# Digital_Online_Clock.net
KiCad netlist of a schematic drawn in EasyEDA Pro
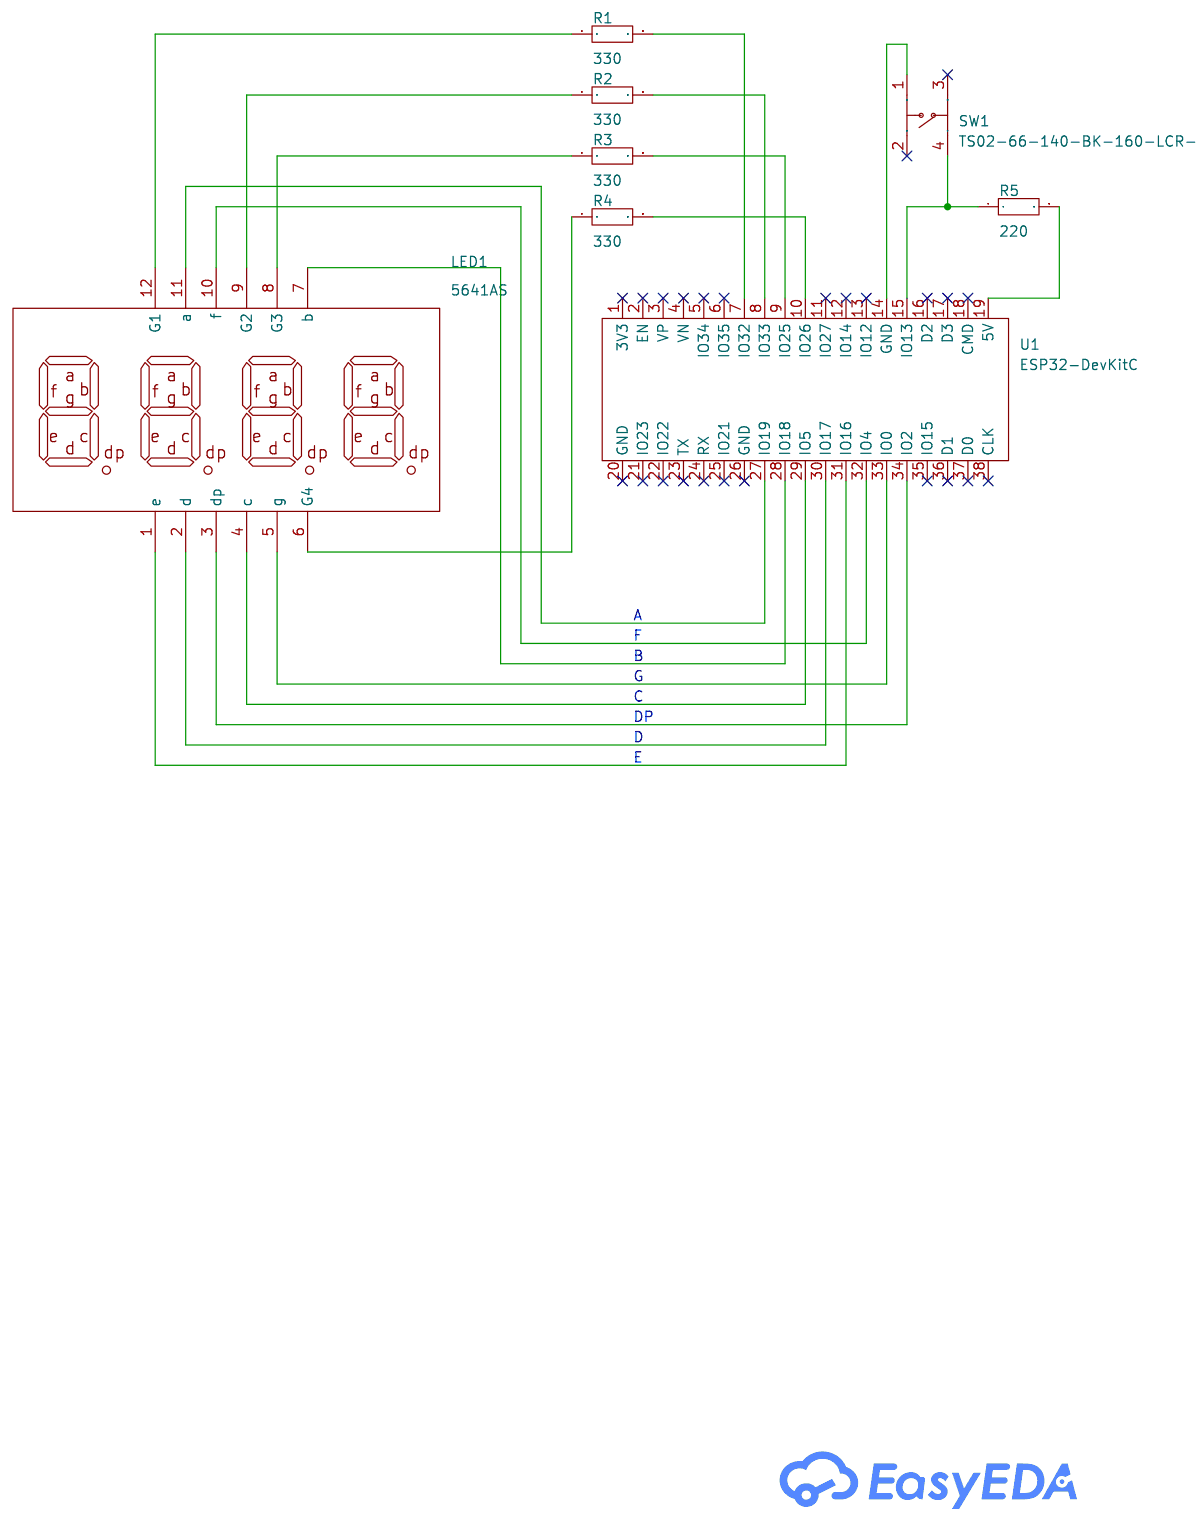
[diagram p0: schematic sheet]

(export (version "E")
  (design (tool "Eeschema 10.0.6"))
  (components
    (comp (ref "LED1")
      (value "5641AS")
      (footprint "easyedapro:LED-SEG-50x19x8mm")
      (description "Illumination Color:-")
      (fields (field (name "Manufacturer Part") "SR420312N/32") (field (name "Manufacturer") "ARKLED(方舟)"))
      (libsource (lib "easyedapro") (part "SR420312N/32"))
    )
    (comp (ref "R1") (value "330") (footprint "easyedapro:R0603") (libsource (lib "easyedapro") (part "Res")))
    (comp (ref "R2") (value "330") (footprint "easyedapro:R0603") (libsource (lib "easyedapro") (part "Res")))
    (comp (ref "R3") (value "330") (footprint "easyedapro:R0603") (libsource (lib "easyedapro") (part "Res")))
    (comp (ref "R4") (value "330") (footprint "easyedapro:R0603") (libsource (lib "easyedapro") (part "Res")))
    (comp (ref "R5") (value "220") (footprint "easyedapro:R0603") (libsource (lib "easyedapro") (part "Res")))
    (comp (ref "SW1")
      (value "TS02-66-140-BK-160-LCR-D")
      (footprint "easyedapro:SW-TH_4P-L6.0-W6.0-P4.50-LS6.5")
      (fields (field (name "Manufacturer") "CUI Devices"))
      (libsource (lib "easyedapro") (part "TS02-66-140-BK-160-LCR-D"))
    )
    (comp (ref "U1")
      (value "ESP32-DevKitC")
      (footprint "easyedapro:BULETM-SMD_ESP32-DEVKITC")
      (fields (field (name "Manufacturer") "ESPRESSIF(乐鑫)"))
      (libsource (lib "easyedapro") (part "ESP32-DEVKITC"))
    )
  )
  (nets
    (net (code "1") (name "Net-(LED1-G1)") (class "Default")
      (node (ref "LED1") (pin "12") (pinfunction "G1_12") (pintype "input"))
      (node (ref "R1") (pin "1") (pinfunction "1_1") (pintype "input"))
    )
    (net (code "2") (name "Net-(LED1-G2)") (class "Default")
      (node (ref "LED1") (pin "9") (pinfunction "G2_9") (pintype "input"))
      (node (ref "R2") (pin "1") (pinfunction "1_1") (pintype "input"))
    )
    (net (code "3") (name "Net-(LED1-G3)") (class "Default")
      (node (ref "LED1") (pin "8") (pinfunction "G3_8") (pintype "input"))
      (node (ref "R3") (pin "1") (pinfunction "1_1") (pintype "input"))
    )
    (net (code "4") (name "Net-(LED1-G4)") (class "Default")
      (node (ref "LED1") (pin "6") (pinfunction "G4_6") (pintype "input"))
      (node (ref "R4") (pin "1") (pinfunction "1_1") (pintype "input"))
    )
    (net (code "5") (name "Net-(LED1-a)") (class "Default")
      (node (ref "LED1") (pin "11") (pinfunction "a_11") (pintype "input"))
      (node (ref "U1") (pin "27") (pinfunction "IO19_27") (pintype "unspecified"))
    )
    (net (code "6") (name "Net-(LED1-b)") (class "Default")
      (node (ref "LED1") (pin "7") (pinfunction "b_7") (pintype "input"))
      (node (ref "U1") (pin "28") (pinfunction "IO18_28") (pintype "unspecified"))
    )
    (net (code "7") (name "Net-(LED1-c)") (class "Default")
      (node (ref "LED1") (pin "4") (pinfunction "c_4") (pintype "input"))
      (node (ref "U1") (pin "29") (pinfunction "IO5_29") (pintype "unspecified"))
    )
    (net (code "8") (name "Net-(LED1-d)") (class "Default")
      (node (ref "LED1") (pin "2") (pinfunction "d_2") (pintype "input"))
      (node (ref "U1") (pin "30") (pinfunction "IO17_30") (pintype "unspecified"))
    )
    (net (code "9") (name "Net-(LED1-dp)") (class "Default")
      (node (ref "LED1") (pin "3") (pinfunction "dp_3") (pintype "input"))
      (node (ref "U1") (pin "34") (pinfunction "IO2_34") (pintype "unspecified"))
    )
    (net (code "10") (name "Net-(LED1-e)") (class "Default")
      (node (ref "LED1") (pin "1") (pinfunction "e_1") (pintype "input"))
      (node (ref "U1") (pin "31") (pinfunction "IO16_31") (pintype "unspecified"))
    )
    (net (code "11") (name "Net-(LED1-f)") (class "Default")
      (node (ref "LED1") (pin "10") (pinfunction "f_10") (pintype "input"))
      (node (ref "U1") (pin "32") (pinfunction "IO4_32") (pintype "unspecified"))
    )
    (net (code "12") (name "Net-(LED1-g)") (class "Default")
      (node (ref "LED1") (pin "5") (pinfunction "g_5") (pintype "input"))
      (node (ref "U1") (pin "33") (pinfunction "IO0_33") (pintype "unspecified"))
    )
    (net (code "13") (name "Net-(SW1-Pad1)") (class "Default")
      (node (ref "SW1") (pin "1") (pinfunction "1_1") (pintype "unspecified"))
      (node (ref "U1") (pin "14") (pinfunction "GND_14") (pintype "unspecified"))
    )
    (net (code "14") (name "Net-(U1-5V)") (class "Default")
      (node (ref "R5") (pin "2") (pinfunction "2_2") (pintype "input"))
      (node (ref "U1") (pin "19") (pinfunction "5V_19") (pintype "unspecified"))
    )
    (net (code "15") (name "Net-(U1-IO13)") (class "Default")
      (node (ref "R5") (pin "1") (pinfunction "1_1") (pintype "input"))
      (node (ref "SW1") (pin "4") (pinfunction "4_4") (pintype "unspecified"))
      (node (ref "U1") (pin "15") (pinfunction "IO13_15") (pintype "unspecified"))
    )
    (net (code "16") (name "Net-(U1-IO25)") (class "Default")
      (node (ref "R3") (pin "2") (pinfunction "2_2") (pintype "input"))
      (node (ref "U1") (pin "9") (pinfunction "IO25_9") (pintype "unspecified"))
    )
    (net (code "17") (name "Net-(U1-IO26)") (class "Default")
      (node (ref "R4") (pin "2") (pinfunction "2_2") (pintype "input"))
      (node (ref "U1") (pin "10") (pinfunction "IO26_10") (pintype "unspecified"))
    )
    (net (code "18") (name "Net-(U1-IO32)") (class "Default")
      (node (ref "R1") (pin "2") (pinfunction "2_2") (pintype "input"))
      (node (ref "U1") (pin "7") (pinfunction "IO32_7") (pintype "unspecified"))
    )
    (net (code "19") (name "Net-(U1-IO33)") (class "Default")
      (node (ref "R2") (pin "2") (pinfunction "2_2") (pintype "input"))
      (node (ref "U1") (pin "8") (pinfunction "IO33_8") (pintype "unspecified"))
    )
    (net (code "20") (name "unconnected-(SW1-Pad2)") (class "Default")
      (node (ref "SW1") (pin "2") (pinfunction "2_2") (pintype "unspecified+no_connect"))
    )
    (net (code "21") (name "unconnected-(SW1-Pad3)") (class "Default")
      (node (ref "SW1") (pin "3") (pinfunction "3_3") (pintype "unspecified+no_connect"))
    )
    (net (code "22") (name "unconnected-(U1-3V3-Pad1)") (class "Default")
      (node (ref "U1") (pin "1") (pinfunction "3V3_1") (pintype "unspecified+no_connect"))
    )
    (net (code "23") (name "unconnected-(U1-CLK-Pad38)") (class "Default")
      (node (ref "U1") (pin "38") (pinfunction "CLK_38") (pintype "unspecified+no_connect"))
    )
    (net (code "24") (name "unconnected-(U1-CMD-Pad18)") (class "Default")
      (node (ref "U1") (pin "18") (pinfunction "CMD_18") (pintype "unspecified+no_connect"))
    )
    (net (code "25") (name "unconnected-(U1-D0-Pad37)") (class "Default")
      (node (ref "U1") (pin "37") (pinfunction "D0_37") (pintype "unspecified+no_connect"))
    )
    (net (code "26") (name "unconnected-(U1-D1-Pad36)") (class "Default")
      (node (ref "U1") (pin "36") (pinfunction "D1_36") (pintype "unspecified+no_connect"))
    )
    (net (code "27") (name "unconnected-(U1-D2-Pad16)") (class "Default")
      (node (ref "U1") (pin "16") (pinfunction "D2_16") (pintype "unspecified+no_connect"))
    )
    (net (code "28") (name "unconnected-(U1-D3-Pad17)") (class "Default")
      (node (ref "U1") (pin "17") (pinfunction "D3_17") (pintype "unspecified+no_connect"))
    )
    (net (code "29") (name "unconnected-(U1-EN-Pad2)") (class "Default")
      (node (ref "U1") (pin "2") (pinfunction "EN_2") (pintype "unspecified+no_connect"))
    )
    (net (code "30") (name "unconnected-(U1-GND-Pad20)") (class "Default")
      (node (ref "U1") (pin "20") (pinfunction "GND_20") (pintype "unspecified+no_connect"))
    )
    (net (code "31") (name "unconnected-(U1-GND-Pad26)") (class "Default")
      (node (ref "U1") (pin "26") (pinfunction "GND_26") (pintype "unspecified+no_connect"))
    )
    (net (code "32") (name "unconnected-(U1-IO12-Pad13)") (class "Default")
      (node (ref "U1") (pin "13") (pinfunction "IO12_13") (pintype "unspecified+no_connect"))
    )
    (net (code "33") (name "unconnected-(U1-IO14-Pad12)") (class "Default")
      (node (ref "U1") (pin "12") (pinfunction "IO14_12") (pintype "unspecified+no_connect"))
    )
    (net (code "34") (name "unconnected-(U1-IO15-Pad35)") (class "Default")
      (node (ref "U1") (pin "35") (pinfunction "IO15_35") (pintype "unspecified+no_connect"))
    )
    (net (code "35") (name "unconnected-(U1-IO21-Pad25)") (class "Default")
      (node (ref "U1") (pin "25") (pinfunction "IO21_25") (pintype "unspecified+no_connect"))
    )
    (net (code "36") (name "unconnected-(U1-IO22-Pad22)") (class "Default")
      (node (ref "U1") (pin "22") (pinfunction "IO22_22") (pintype "unspecified+no_connect"))
    )
    (net (code "37") (name "unconnected-(U1-IO23-Pad21)") (class "Default")
      (node (ref "U1") (pin "21") (pinfunction "IO23_21") (pintype "unspecified+no_connect"))
    )
    (net (code "38") (name "unconnected-(U1-IO27-Pad11)") (class "Default")
      (node (ref "U1") (pin "11") (pinfunction "IO27_11") (pintype "unspecified+no_connect"))
    )
    (net (code "39") (name "unconnected-(U1-IO34-Pad5)") (class "Default")
      (node (ref "U1") (pin "5") (pinfunction "IO34_5") (pintype "unspecified+no_connect"))
    )
    (net (code "40") (name "unconnected-(U1-IO35-Pad6)") (class "Default")
      (node (ref "U1") (pin "6") (pinfunction "IO35_6") (pintype "unspecified+no_connect"))
    )
    (net (code "41") (name "unconnected-(U1-RX-Pad24)") (class "Default")
      (node (ref "U1") (pin "24") (pinfunction "RX_24") (pintype "unspecified+no_connect"))
    )
    (net (code "42") (name "unconnected-(U1-TX-Pad23)") (class "Default")
      (node (ref "U1") (pin "23") (pinfunction "TX_23") (pintype "unspecified+no_connect"))
    )
    (net (code "43") (name "unconnected-(U1-VN-Pad4)") (class "Default")
      (node (ref "U1") (pin "4") (pinfunction "VN_4") (pintype "unspecified+no_connect"))
    )
    (net (code "44") (name "unconnected-(U1-VP-Pad3)") (class "Default")
      (node (ref "U1") (pin "3") (pinfunction "VP_3") (pintype "unspecified+no_connect"))
    )
  )
)
